# Power.net
KiCad netlist of a schematic drawn in Altium Designer
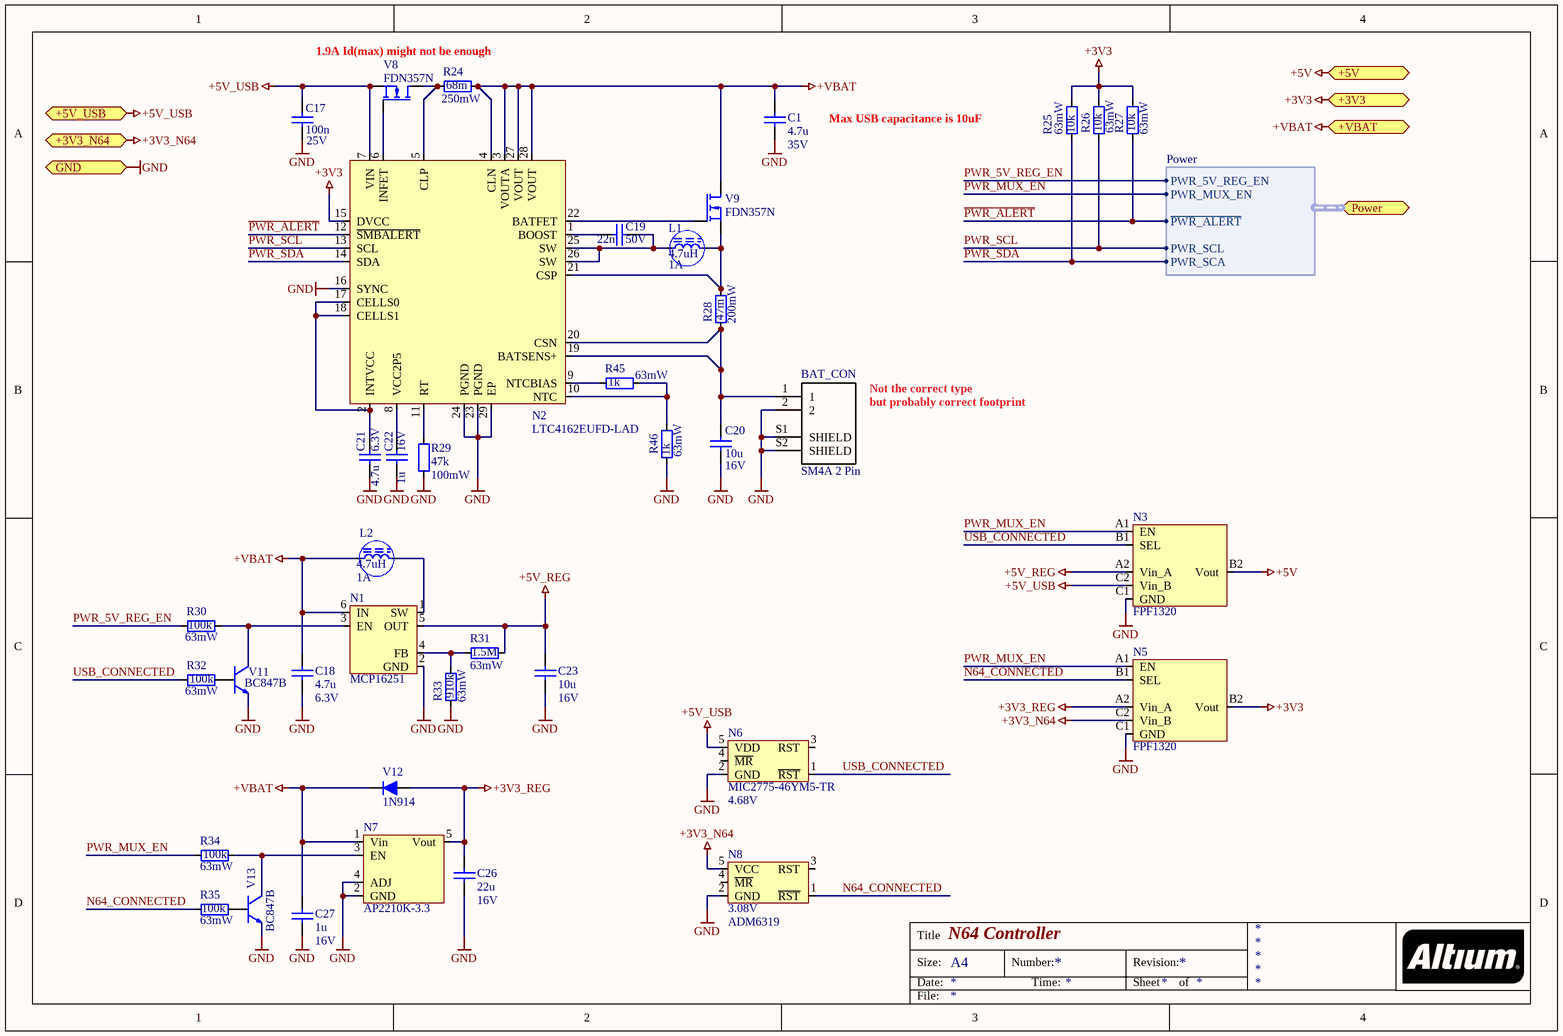
[diagram p0: Power.SchDoc]

(export (version "E")
  (design (tool "Eeschema 10.0.6"))
  (components
    (comp (ref "BAT_CON")
      (value "X_SMD_SM4A_2PIN_MALE")
      (footprint "SMD_CON_SM4A_2PIN_MALE")
      (description "Connector Header Surface Mount, Right Angle 2 position 0.059\" (1.50mm)")
      (fields (field (name "TYPE") "SM4A 2 Pin"))
      (libsource (lib "AM") (part "X_SMD_SM4A_2PIN_MALE"))
    )
    (comp (ref "C1")
      (value "4.7u")
      (footprint "SMD_CAP_0805")
      (description "SMD Capacitor, Ceramic")
      (fields (field (name "VALUE2") "35V") (field (name "Comment") "C_SMD_CER_4U7_35V_10%_X7R_0805"))
      (libsource (lib "AM") (part "C_SMD_CER_4U7_35V_10%_X7R_0805"))
    )
    (comp (ref "C17")
      (value "100n")
      (footprint "SMD_CAP_0402")
      (description "0.1µF ±10% 25V Ceramic Capacitor X7R 0402 (1005 Metric)")
      (fields (field (name "VALUE2") "25V") (field (name "Comment") "C_SMD_CER_100N_25V_10%_X7R_0402"))
      (libsource (lib "AM") (part "C_SMD_CER_100N_25V_10%_X7R_0402"))
    )
    (comp (ref "C18")
      (value "4.7u")
      (footprint "SMD_CAP_0603")
      (fields (field (name "VALUE2") "6.3V") (field (name "Comment") "C_SMD_CER_4U7_6V3_10%_X5R_0603"))
      (libsource (lib "AM") (part "C_SMD_CER_4U7_6V3_10%_X5R_0603"))
    )
    (comp (ref "C19")
      (value "22n")
      (footprint "SMD_CAP_0402")
      (description "0.022µF ±10% 50V Ceramic Capacitor X7R 0402 (1005 Metric)")
      (fields (field (name "VALUE2") "50V") (field (name "Comment") "C_SMD_CER_22N_50V_10%_X7R_0402"))
      (libsource (lib "AM") (part "C_SMD_CER_22N_50V_10%_X7R_0402"))
    )
    (comp (ref "C20")
      (value "10u")
      (footprint "SMD_CAP_0805")
      (description "10µF ±10% 16V Ceramic Capacitor X7R 0805 (2012 Metric)")
      (fields (field (name "VALUE2") "16V") (field (name "Comment") "C_SMD_CER_10U_16V_10%_X7R_0805"))
      (libsource (lib "AM") (part "C_SMD_CER_10U_16V_10%_X7R_0805"))
    )
    (comp (ref "C21")
      (value "4.7u")
      (footprint "SMD_CAP_0603")
      (fields (field (name "VALUE2") "6.3V") (field (name "Comment") "C_SMD_CER_4U7_6V3_10%_X5R_0603"))
      (libsource (lib "AM") (part "C_SMD_CER_4U7_6V3_10%_X5R_0603"))
    )
    (comp (ref "C22")
      (value "1u")
      (footprint "SMD_CAP_0603")
      (description "1µF ±10% 16V Ceramic Capacitor X7R 0603 (1608 Metric)")
      (fields (field (name "VALUE2") "16V") (field (name "Comment") "C_SMD_CER_1U_16V_10%_X7R_0603"))
      (libsource (lib "AM") (part "C_SMD_CER_1U_16V_10%_X7R_0603"))
    )
    (comp (ref "C23")
      (value "10u")
      (footprint "SMD_CAP_0805")
      (description "10µF ±10% 16V Ceramic Capacitor X7R 0805 (2012 Metric)")
      (fields (field (name "VALUE2") "16V") (field (name "Comment") "C_SMD_CER_10U_16V_10%_X7R_0805"))
      (libsource (lib "AM") (part "C_SMD_CER_10U_16V_10%_X7R_0805"))
    )
    (comp (ref "C26")
      (value "22u")
      (footprint "SMD_CAP_0805")
      (description "22µF ±10% 16V Ceramic Capacitor X5R 0805 (2012 Metric)")
      (fields (field (name "VALUE2") "16V") (field (name "Comment") "C_SMD_CER_22U_16V_10%_X5R_0805"))
      (libsource (lib "AM") (part "C_SMD_CER_22U_16V_10%_X5R_0805"))
    )
    (comp (ref "C27")
      (value "1u")
      (footprint "SMD_CAP_0603")
      (description "1µF ±10% 16V Ceramic Capacitor X7R 0603 (1608 Metric)")
      (fields (field (name "VALUE2") "16V") (field (name "Comment") "C_SMD_CER_1U_16V_10%_X7R_0603"))
      (libsource (lib "AM") (part "C_SMD_CER_1U_16V_10%_X7R_0603"))
    )
    (comp (ref "L1")
      (value "4.7uH")
      (footprint "SMD_IND_0806")
      (description "SMD Inductor")
      (fields (field (name "VALUE2") "1A") (field (name "Comment") "L_SMD_FERRITE_SHIELD_4U7_1A_20%_0806"))
      (libsource (lib "AM") (part "L_SMD_FERRITE_SHIELD_4U7_1A_20%_0806"))
    )
    (comp (ref "L2")
      (value "4.7uH")
      (footprint "SMD_IND_0806")
      (description "SMD Inductor")
      (fields (field (name "VALUE2") "1A") (field (name "Comment") "L_SMD_FERRITE_SHIELD_4U7_1A_20%_0806"))
      (libsource (lib "AM") (part "L_SMD_FERRITE_SHIELD_4U7_1A_20%_0806"))
    )
    (comp (ref "N1")
      (value "N_MCP16251T_SOT-23-6")
      (footprint "SMD_SOT_23_6")
      (description "Boost Switching Regulator IC Positive Adjustable 1.8V 1 Output 100mA (Switch) SOT-23-6")
      (fields (field (name "TYPE") "MCP16251"))
      (libsource (lib "AM") (part "N_MCP16251T_SOT-23-6"))
    )
    (comp (ref "N2")
      (value "N_LTC4162EUFD-LAD_QFN-28")
      (footprint "QFN50P400X500X80_HS-29N")
      (description "35V/3.2A MULTI-CELL LITHIUM-ION")
      (fields (field (name "TYPE") "LTC4162EUFD-LAD"))
      (libsource (lib "AM") (part "N_LTC4162EUFD-LAD_QFN-28"))
    )
    (comp (ref "N3")
      (value "*")
      (footprint "SMD_WLCSP_6_1.0X1.5")
      (description "Power Switch/Driver 2:1 P-Channel 1.5A 6-WLCSP (0.96x1.66)")
      (fields (field (name "TYPE") "FPF1320"))
      (libsource (lib "AM") (part "N_FPF1320UCX_WLCSP-6"))
    )
    (comp (ref "N5")
      (value "*")
      (footprint "SMD_WLCSP_6_1.0X1.5")
      (description "Power Switch/Driver 2:1 P-Channel 1.5A 6-WLCSP (0.96x1.66)")
      (fields (field (name "TYPE") "FPF1320"))
      (libsource (lib "AM") (part "N_FPF1320UCX_WLCSP-6"))
    )
    (comp (ref "N6")
      (value "4.68V")
      (footprint "SMD_SOT_23_5")
      (description "IC SUPERVISOR MICROPOWER SOT23-5")
      (fields (field (name "TYPE") "MIC2775-46YM5-TR") (field (name "Comment") "N_MIC2775-46YM5-TR_SOT-23-5"))
      (libsource (lib "AM") (part "N_MIC2775-46YM5-TR_SOT-23-5"))
    )
    (comp (ref "N7")
      (value "AP2210K-3.3")
      (footprint "SMD_SOT_23_5")
      (description "IC REG LINEAR 3.3V 300MA SOT23-5")
      (fields (field (name "TYPE") "AP2210K-3.3"))
      (libsource (lib "AM") (part "N_AP2210K-3.3_SOT-23-5"))
    )
    (comp (ref "N8")
      (value "3.08V")
      (footprint "SMD_SOT_23_5")
      (description "IC SUPERVISOR MANUAL RST SOT23-5")
      (fields (field (name "TYPE") "ADM6319") (field (name "Comment") "N_ADM6319B31ARJZ-RL7_SOT-23-5"))
      (libsource (lib "AM") (part "N_ADM6319B31ARJZ-RL7_SOT-23-5"))
    )
    (comp (ref "R24")
      (value "68m")
      (footprint "SMD_RES_0603")
      (description "68 mOhms ±1% 0.25W, 1/4W Chip Resistor 0603 (1608 Metric) Current Sense Thin Film")
      (fields
        (field (name "VALUE2") "250mW")
        (field (name "Comment") "R_SMD_THINFILM_0E068_0W25_1%_350PPM_0603")
      )
      (libsource (lib "AM") (part "R_SMD_THINFILM_0E068_0W25_1%_350PPM_0603"))
    )
    (comp (ref "R25")
      (value "10k")
      (footprint "SMD_RES_0402")
      (description "SMD Resistor")
      (fields
        (field (name "VALUE2") "63mW")
        (field (name "Comment") "R_SMD_THINFILM_10K_0W063_0%5_25PPM_0402")
      )
      (libsource (lib "AM") (part "R_SMD_THINFILM_10K_0W063_0%5_25PPM_0402"))
    )
    (comp (ref "R26")
      (value "10k")
      (footprint "SMD_RES_0402")
      (description "SMD Resistor")
      (fields
        (field (name "VALUE2") "63mW")
        (field (name "Comment") "R_SMD_THINFILM_10K_0W063_0%5_25PPM_0402")
      )
      (libsource (lib "AM") (part "R_SMD_THINFILM_10K_0W063_0%5_25PPM_0402"))
    )
    (comp (ref "R27")
      (value "10k")
      (footprint "SMD_RES_0402")
      (description "SMD Resistor")
      (fields
        (field (name "VALUE2") "63mW")
        (field (name "Comment") "R_SMD_THINFILM_10K_0W063_0%5_25PPM_0402")
      )
      (libsource (lib "AM") (part "R_SMD_THINFILM_10K_0W063_0%5_25PPM_0402"))
    )
    (comp (ref "R28")
      (value "47m")
      (footprint "SMD_RES_0603")
      (fields
        (field (name "VALUE2") "200mW")
        (field (name "Comment") "R_SMD_THICKFILM_0E047_0W2_1%_200PPM_0603")
      )
      (libsource (lib "AM") (part "R_SMD_THICKFILM_0E047_0W2_1%_200PPM_0603"))
    )
    (comp (ref "R29")
      (value "47k")
      (footprint "SMD_RES_0402")
      (description "47 kOhms ±0.5% 0.063W, 1/16W Chip Resistor 0402 (1005 Metric) Automotive AEC-Q200 Thin Film")
      (fields
        (field (name "VALUE2") "100mW")
        (field (name "Comment") "R_SMD_THINFILM_47K_0W1_0%5_25PPM_0402")
      )
      (libsource (lib "AM") (part "R_SMD_THINFILM_47K_0W1_0%5_25PPM_0402"))
    )
    (comp (ref "R30")
      (value "100k")
      (footprint "SMD_RES_0402")
      (description "100 kOhms ±1% 0.063W, 1/16W Chip Resistor 0402 (1005 Metric) Thin Film")
      (fields
        (field (name "VALUE2") "63mW")
        (field (name "Comment") "R_SMD_THINFILM_100K_0W063_1%_50PPM_0402")
      )
      (libsource (lib "AM") (part "R_SMD_THINFILM_100K_0W063_1%_50PPM_0402"))
    )
    (comp (ref "R31")
      (value "1.5M")
      (footprint "SMD_RES_0402")
      (description "1.5 MOhms ±1% 0.1W, 1/10W Chip Resistor 0402 (1005 Metric) Anti-Sulfur Thin Film")
      (fields
        (field (name "VALUE2") "63mW")
        (field (name "Comment") "R_SMD_THINFILM_1M5_0W063_1%_50PPM_0402")
      )
      (libsource (lib "AM") (part "R_SMD_THINFILM_1M5_0W063_1%_50PPM_0402"))
    )
    (comp (ref "R32")
      (value "100k")
      (footprint "SMD_RES_0402")
      (description "100 kOhms ±1% 0.063W, 1/16W Chip Resistor 0402 (1005 Metric) Thin Film")
      (fields
        (field (name "VALUE2") "63mW")
        (field (name "Comment") "R_SMD_THINFILM_100K_0W063_1%_50PPM_0402")
      )
      (libsource (lib "AM") (part "R_SMD_THINFILM_100K_0W063_1%_50PPM_0402"))
    )
    (comp (ref "R33")
      (value "910k")
      (footprint "SMD_RES_0402")
      (description "910 kOhms ±1% 0.063W, 1/16W Chip Resistor 0402 (1005 Metric) Moisture Resistant Thick Film")
      (fields
        (field (name "VALUE2") "63mW")
        (field (name "Comment") "R_SMD_THICKFILM_910K_0W063_1%_100PPM_0402")
      )
      (libsource (lib "AM") (part "R_SMD_THICKFILM_910K_0W063_1%_100PPM_0402"))
    )
    (comp (ref "R34")
      (value "100k")
      (footprint "SMD_RES_0402")
      (description "100 kOhms ±1% 0.063W, 1/16W Chip Resistor 0402 (1005 Metric) Thin Film")
      (fields
        (field (name "VALUE2") "63mW")
        (field (name "Comment") "R_SMD_THINFILM_100K_0W063_1%_50PPM_0402")
      )
      (libsource (lib "AM") (part "R_SMD_THINFILM_100K_0W063_1%_50PPM_0402"))
    )
    (comp (ref "R35")
      (value "100k")
      (footprint "SMD_RES_0402")
      (description "100 kOhms ±1% 0.063W, 1/16W Chip Resistor 0402 (1005 Metric) Thin Film")
      (fields
        (field (name "VALUE2") "63mW")
        (field (name "Comment") "R_SMD_THINFILM_100K_0W063_1%_50PPM_0402")
      )
      (libsource (lib "AM") (part "R_SMD_THINFILM_100K_0W063_1%_50PPM_0402"))
    )
    (comp (ref "R45")
      (value "1k")
      (footprint "SMD_RES_0402")
      (description "1 kOhms ±0.5% 0.063W, 1/16W Chip Resistor 0402 (1005 Metric) Automotive AEC-Q200 Thin Film")
      (fields
        (field (name "VALUE2") "63mW")
        (field (name "Comment") "R_SMD_THINFILM_1K_0W063_0%5_25PPM_0402")
      )
      (libsource (lib "AM") (part "R_SMD_THINFILM_1K_0W063_0%5_25PPM_0402"))
    )
    (comp (ref "R46")
      (value "1k")
      (footprint "SMD_RES_0402")
      (description "1 kOhms ±0.5% 0.063W, 1/16W Chip Resistor 0402 (1005 Metric) Automotive AEC-Q200 Thin Film")
      (fields
        (field (name "VALUE2") "63mW")
        (field (name "Comment") "R_SMD_THINFILM_1K_0W063_0%5_25PPM_0402")
      )
      (libsource (lib "AM") (part "R_SMD_THINFILM_1K_0W063_0%5_25PPM_0402"))
    )
    (comp (ref "V8")
      (value "V_SMD_FET_NMOS_FDN357N_30V_1A9_4NC2_0W5_SOT-23-3")
      (footprint "SMD_SOT_23_3")
      (description "N-Channel Logic Level Enhancement Mode Field Effect Transistor")
      (fields (field (name "TYPE") "FDN357N"))
      (libsource (lib "AM") (part "V_SMD_FET_NMOS_FDN357N_30V_1A9_4NC2_0W5_SOT-23-3"))
    )
    (comp (ref "V9")
      (value "V_SMD_FET_NMOS_FDN357N_30V_1A9_4NC2_0W5_SOT-23-3")
      (footprint "SMD_SOT_23_3")
      (description "N-Channel Logic Level Enhancement Mode Field Effect Transistor")
      (fields (field (name "TYPE") "FDN357N"))
      (libsource (lib "AM") (part "V_SMD_FET_NMOS_FDN357N_30V_1A9_4NC2_0W5_SOT-23-3"))
    )
    (comp (ref "V11")
      (value "V_SMD_TRANS_NPN_BC847B_50V_0A2_SOT-23-3")
      (footprint "SMD_SOT_23_3")
      (description "NPN Transistor")
      (fields (field (name "TYPE") "BC847B"))
      (libsource (lib "AM") (part "V_SMD_TRANS_NPN_BC847B_50V_0A2_SOT-23-3"))
    )
    (comp (ref "V12")
      (value "V_SMD_DIODE_1N914_75V_0A15_SOD-323")
      (footprint "SMD_SOD_323")
      (description "SMD Diode, 75V, 0.15A")
      (fields (field (name "TYPE") "1N914"))
      (libsource (lib "AM") (part "V_SMD_DIODE_1N914_75V_0A15_SOD-323"))
    )
    (comp (ref "V13")
      (value "V_SMD_TRANS_NPN_BC847B_50V_0A2_SOT-23-3")
      (footprint "SMD_SOT_23_3")
      (description "NPN Transistor")
      (fields (field (name "TYPE") "BC847B"))
      (libsource (lib "AM") (part "V_SMD_TRANS_NPN_BC847B_50V_0A2_SOT-23-3"))
    )
  )
  (nets
    (net (code "2") (name "+3V3") (class "Default")
      (node (ref "N2") (pin "15") (pinfunction "DVCC_15") (pintype "passive"))
      (node (ref "N5") (pin "B2") (pinfunction "Vout_B2") (pintype "passive"))
      (node (ref "R25") (pin "2") (pinfunction "2_2") (pintype "passive"))
      (node (ref "R26") (pin "2") (pinfunction "2_2") (pintype "passive"))
      (node (ref "R27") (pin "2") (pinfunction "2_2") (pintype "passive"))
    )
    (net (code "3") (name "+3V3_N64") (class "Default")
      (node (ref "N5") (pin "C2") (pinfunction "Vin_B_C2") (pintype "passive"))
      (node (ref "N8") (pin "5") (pinfunction "VCC_5") (pintype "passive"))
    )
    (net (code "4") (name "+3V3_REG") (class "Default")
      (node (ref "C26") (pin "2") (pinfunction "2_2") (pintype "passive"))
      (node (ref "N5") (pin "A2") (pinfunction "Vin_A_A2") (pintype "passive"))
      (node (ref "N7") (pin "5") (pinfunction "Vout_5") (pintype "passive"))
      (node (ref "V12") (pin "1") (pinfunction "1_1") (pintype "passive"))
    )
    (net (code "5") (name "+5V") (class "Default")
      (node (ref "N3") (pin "B2") (pinfunction "Vout_B2") (pintype "passive"))
    )
    (net (code "6") (name "+5V_REG") (class "Default")
      (node (ref "C23") (pin "2") (pinfunction "2_2") (pintype "passive"))
      (node (ref "N1") (pin "5") (pinfunction "OUT_5") (pintype "passive"))
      (node (ref "N3") (pin "A2") (pinfunction "Vin_A_A2") (pintype "passive"))
      (node (ref "R31") (pin "1") (pinfunction "1_1") (pintype "passive"))
    )
    (net (code "7") (name "+5V_USB") (class "Default")
      (node (ref "C17") (pin "2") (pinfunction "2_2") (pintype "passive"))
      (node (ref "N2") (pin "7") (pinfunction "VIN_7") (pintype "passive"))
      (node (ref "N3") (pin "C2") (pinfunction "Vin_B_C2") (pintype "passive"))
      (node (ref "N6") (pin "5") (pinfunction "VDD_5") (pintype "passive"))
      (node (ref "V8") (pin "2") (pinfunction "Source_2") (pintype "passive"))
    )
    (net (code "8") (name "+VBAT") (class "Default")
      (node (ref "C1") (pin "2") (pinfunction "2_2") (pintype "passive"))
      (node (ref "C18") (pin "2") (pinfunction "2_2") (pintype "passive"))
      (node (ref "C27") (pin "2") (pinfunction "2_2") (pintype "passive"))
      (node (ref "L2") (pin "1") (pinfunction "1_1") (pintype "passive"))
      (node (ref "N1") (pin "6") (pinfunction "IN_6") (pintype "passive"))
      (node (ref "N2") (pin "27") (pinfunction "VOUT_27") (pintype "passive"))
      (node (ref "N2") (pin "28") (pinfunction "VOUT_28") (pintype "passive"))
      (node (ref "N2") (pin "3") (pinfunction "VOUTA_3") (pintype "passive"))
      (node (ref "N2") (pin "4") (pinfunction "CLN_4") (pintype "passive"))
      (node (ref "N7") (pin "1") (pinfunction "Vin_1") (pintype "passive"))
      (node (ref "R24") (pin "2") (pinfunction "2_2") (pintype "passive"))
      (node (ref "V12") (pin "2") (pinfunction "2_2") (pintype "passive"))
      (node (ref "V9") (pin "3") (pinfunction "Drain_3") (pintype "passive"))
    )
    (net (code "9") (name "/N64_CONNECTED") (class "Default")
      (node (ref "N5") (pin "B1") (pinfunction "SEL_B1") (pintype "passive"))
      (node (ref "N8") (pin "1") (pinfunction "~{RST}_1") (pintype "passive"))
      (node (ref "R35") (pin "1") (pinfunction "1_1") (pintype "passive"))
    )
    (net (code "10") (name "/PWR_5V_REG_EN") (class "Default")
      (node (ref "R30") (pin "1") (pinfunction "1_1") (pintype "passive"))
    )
    (net (code "11") (name "/PWR_MUX_EN") (class "Default")
      (node (ref "N3") (pin "A1") (pinfunction "EN_A1") (pintype "passive"))
      (node (ref "N5") (pin "A1") (pinfunction "EN_A1") (pintype "passive"))
      (node (ref "R34") (pin "1") (pinfunction "1_1") (pintype "passive"))
    )
    (net (code "12") (name "/PWR_SCL") (class "Default")
      (node (ref "N2") (pin "13") (pinfunction "SCL_13") (pintype "passive"))
      (node (ref "R26") (pin "1") (pinfunction "1_1") (pintype "passive"))
    )
    (net (code "13") (name "/PWR_SDA") (class "Default")
      (node (ref "N2") (pin "14") (pinfunction "SDA_14") (pintype "passive"))
      (node (ref "R25") (pin "1") (pinfunction "1_1") (pintype "passive"))
    )
    (net (code "14") (name "/USB_CONNECTED") (class "Default")
      (node (ref "N3") (pin "B1") (pinfunction "SEL_B1") (pintype "passive"))
      (node (ref "N6") (pin "1") (pinfunction "~{RST}_1") (pintype "passive"))
      (node (ref "R32") (pin "1") (pinfunction "1_1") (pintype "passive"))
    )
    (net (code "16") (name "/~{PWR_ALERT}") (class "Default")
      (node (ref "N2") (pin "12") (pinfunction "~{SMBALERT}_12") (pintype "passive"))
      (node (ref "R27") (pin "1") (pinfunction "1_1") (pintype "passive"))
    )
    (net (code "17") (name "GND") (class "Default")
      (node (ref "BAT_CON") (pin "2") (pinfunction "2_2") (pintype "passive"))
      (node (ref "BAT_CON") (pin "S1") (pinfunction "SHIELD_S1") (pintype "passive"))
      (node (ref "BAT_CON") (pin "S2") (pinfunction "SHIELD_S2") (pintype "passive"))
      (node (ref "C1") (pin "1") (pinfunction "1_1") (pintype "passive"))
      (node (ref "C17") (pin "1") (pinfunction "1_1") (pintype "passive"))
      (node (ref "C18") (pin "1") (pinfunction "1_1") (pintype "passive"))
      (node (ref "C20") (pin "1") (pinfunction "1_1") (pintype "passive"))
      (node (ref "C21") (pin "1") (pinfunction "1_1") (pintype "passive"))
      (node (ref "C22") (pin "1") (pinfunction "1_1") (pintype "passive"))
      (node (ref "C23") (pin "1") (pinfunction "1_1") (pintype "passive"))
      (node (ref "C26") (pin "1") (pinfunction "1_1") (pintype "passive"))
      (node (ref "C27") (pin "1") (pinfunction "1_1") (pintype "passive"))
      (node (ref "N1") (pin "2") (pinfunction "GND_2") (pintype "passive"))
      (node (ref "N2") (pin "16") (pinfunction "SYNC_16") (pintype "passive"))
      (node (ref "N2") (pin "23") (pinfunction "PGND_23") (pintype "passive"))
      (node (ref "N2") (pin "24") (pinfunction "PGND_24") (pintype "passive"))
      (node (ref "N2") (pin "29") (pinfunction "EP_29") (pintype "passive"))
      (node (ref "N3") (pin "C1") (pinfunction "GND_C1") (pintype "passive"))
      (node (ref "N5") (pin "C1") (pinfunction "GND_C1") (pintype "passive"))
      (node (ref "N6") (pin "2") (pinfunction "GND_2") (pintype "passive"))
      (node (ref "N7") (pin "2") (pinfunction "GND_2") (pintype "passive"))
      (node (ref "N7") (pin "4") (pinfunction "ADJ_4") (pintype "passive"))
      (node (ref "N8") (pin "2") (pinfunction "GND_2") (pintype "passive"))
      (node (ref "R29") (pin "1") (pinfunction "1_1") (pintype "passive"))
      (node (ref "R33") (pin "1") (pinfunction "1_1") (pintype "passive"))
      (node (ref "R46") (pin "1") (pinfunction "1_1") (pintype "passive"))
      (node (ref "V11") (pin "2") (pinfunction "E_2") (pintype "passive"))
      (node (ref "V13") (pin "2") (pinfunction "E_2") (pintype "passive"))
    )
    (net (code "18") (name "Net-(C19-Pad2)") (class "Default")
      (node (ref "C19") (pin "2") (pinfunction "2_2") (pintype "passive"))
      (node (ref "L1") (pin "1") (pinfunction "1_1") (pintype "passive"))
      (node (ref "N2") (pin "25") (pinfunction "SW_25") (pintype "passive"))
      (node (ref "N2") (pin "26") (pinfunction "SW_26") (pintype "passive"))
    )
    (net (code "19") (name "Net-(N1-EN)") (class "Default")
      (node (ref "N1") (pin "3") (pinfunction "EN_3") (pintype "passive"))
      (node (ref "R30") (pin "2") (pinfunction "2_2") (pintype "passive"))
      (node (ref "V11") (pin "3") (pinfunction "C_3") (pintype "passive"))
    )
    (net (code "20") (name "Net-(N1-FB)") (class "Default")
      (node (ref "N1") (pin "4") (pinfunction "FB_4") (pintype "passive"))
      (node (ref "R31") (pin "2") (pinfunction "2_2") (pintype "passive"))
      (node (ref "R33") (pin "2") (pinfunction "2_2") (pintype "passive"))
    )
    (net (code "21") (name "Net-(N1-SW)") (class "Default")
      (node (ref "L2") (pin "2") (pinfunction "2_2") (pintype "passive"))
      (node (ref "N1") (pin "1") (pinfunction "SW_1") (pintype "passive"))
    )
    (net (code "22") (name "Net-(N2-BATFET)") (class "Default")
      (node (ref "N2") (pin "22") (pinfunction "BATFET_22") (pintype "passive"))
      (node (ref "V9") (pin "1") (pinfunction "Gate_1") (pintype "passive"))
    )
    (net (code "23") (name "Net-(N2-BATSENS+)") (class "Default")
      (node (ref "BAT_CON") (pin "1") (pinfunction "1_1") (pintype "passive"))
      (node (ref "C20") (pin "2") (pinfunction "2_2") (pintype "passive"))
      (node (ref "N2") (pin "19") (pinfunction "BATSENS+_19") (pintype "passive"))
      (node (ref "N2") (pin "20") (pinfunction "CSN_20") (pintype "passive"))
      (node (ref "R28") (pin "1") (pinfunction "1_1") (pintype "passive"))
    )
    (net (code "24") (name "Net-(N2-BOOST)") (class "Default")
      (node (ref "C19") (pin "1") (pinfunction "1_1") (pintype "passive"))
      (node (ref "N2") (pin "1") (pinfunction "BOOST_1") (pintype "passive"))
    )
    (net (code "25") (name "Net-(N2-CELLS0)") (class "Default")
      (node (ref "C21") (pin "2") (pinfunction "2_2") (pintype "passive"))
      (node (ref "N2") (pin "17") (pinfunction "CELLS0_17") (pintype "passive"))
      (node (ref "N2") (pin "18") (pinfunction "CELLS1_18") (pintype "passive"))
      (node (ref "N2") (pin "2") (pinfunction "INTVCC_2") (pintype "passive"))
    )
    (net (code "26") (name "Net-(N2-CLP)") (class "Default")
      (node (ref "N2") (pin "5") (pinfunction "CLP_5") (pintype "passive"))
      (node (ref "R24") (pin "1") (pinfunction "1_1") (pintype "passive"))
      (node (ref "V8") (pin "3") (pinfunction "Drain_3") (pintype "passive"))
    )
    (net (code "27") (name "Net-(N2-CSP)") (class "Default")
      (node (ref "L1") (pin "2") (pinfunction "2_2") (pintype "passive"))
      (node (ref "N2") (pin "21") (pinfunction "CSP_21") (pintype "passive"))
      (node (ref "R28") (pin "2") (pinfunction "2_2") (pintype "passive"))
      (node (ref "V9") (pin "2") (pinfunction "Source_2") (pintype "passive"))
    )
    (net (code "28") (name "Net-(N2-INFET)") (class "Default")
      (node (ref "N2") (pin "6") (pinfunction "INFET_6") (pintype "passive"))
      (node (ref "V8") (pin "1") (pinfunction "Gate_1") (pintype "passive"))
    )
    (net (code "29") (name "Net-(N2-NTC)") (class "Default")
      (node (ref "N2") (pin "10") (pinfunction "NTC_10") (pintype "passive"))
      (node (ref "R45") (pin "2") (pinfunction "2_2") (pintype "passive"))
      (node (ref "R46") (pin "2") (pinfunction "2_2") (pintype "passive"))
    )
    (net (code "30") (name "Net-(N2-NTCBIAS)") (class "Default")
      (node (ref "N2") (pin "9") (pinfunction "NTCBIAS_9") (pintype "passive"))
      (node (ref "R45") (pin "1") (pinfunction "1_1") (pintype "passive"))
    )
    (net (code "31") (name "Net-(N2-RT)") (class "Default")
      (node (ref "N2") (pin "11") (pinfunction "RT_11") (pintype "passive"))
      (node (ref "R29") (pin "2") (pinfunction "2_2") (pintype "passive"))
    )
    (net (code "32") (name "Net-(N2-VCC2P5)") (class "Default")
      (node (ref "C22") (pin "2") (pinfunction "2_2") (pintype "passive"))
      (node (ref "N2") (pin "8") (pinfunction "VCC2P5_8") (pintype "passive"))
    )
    (net (code "33") (name "Net-(N7-EN)") (class "Default")
      (node (ref "N7") (pin "3") (pinfunction "EN_3") (pintype "passive"))
      (node (ref "R34") (pin "2") (pinfunction "2_2") (pintype "passive"))
      (node (ref "V13") (pin "3") (pinfunction "C_3") (pintype "passive"))
    )
    (net (code "34") (name "Net-(V11-B)") (class "Default")
      (node (ref "R32") (pin "2") (pinfunction "2_2") (pintype "passive"))
      (node (ref "V11") (pin "1") (pinfunction "B_1") (pintype "passive"))
    )
    (net (code "35") (name "Net-(V13-B)") (class "Default")
      (node (ref "R35") (pin "2") (pinfunction "2_2") (pintype "passive"))
      (node (ref "V13") (pin "1") (pinfunction "B_1") (pintype "passive"))
    )
    (net (code "36") (name "unconnected-(N6-RST-Pad3)") (class "Default")
      (node (ref "N6") (pin "3") (pinfunction "RST_3") (pintype "passive"))
    )
    (net (code "37") (name "unconnected-(N6-~{MR}-Pad4)") (class "Default")
      (node (ref "N6") (pin "4") (pinfunction "~{MR}_4") (pintype "passive"))
    )
    (net (code "38") (name "unconnected-(N8-RST-Pad3)") (class "Default")
      (node (ref "N8") (pin "3") (pinfunction "RST_3") (pintype "passive"))
    )
    (net (code "39") (name "unconnected-(N8-~{MR}-Pad4)") (class "Default")
      (node (ref "N8") (pin "4") (pinfunction "~{MR}_4") (pintype "passive"))
    )
  )
)
